# ezo_single.net
KiCad netlist of a schematic drawn in EAGLE
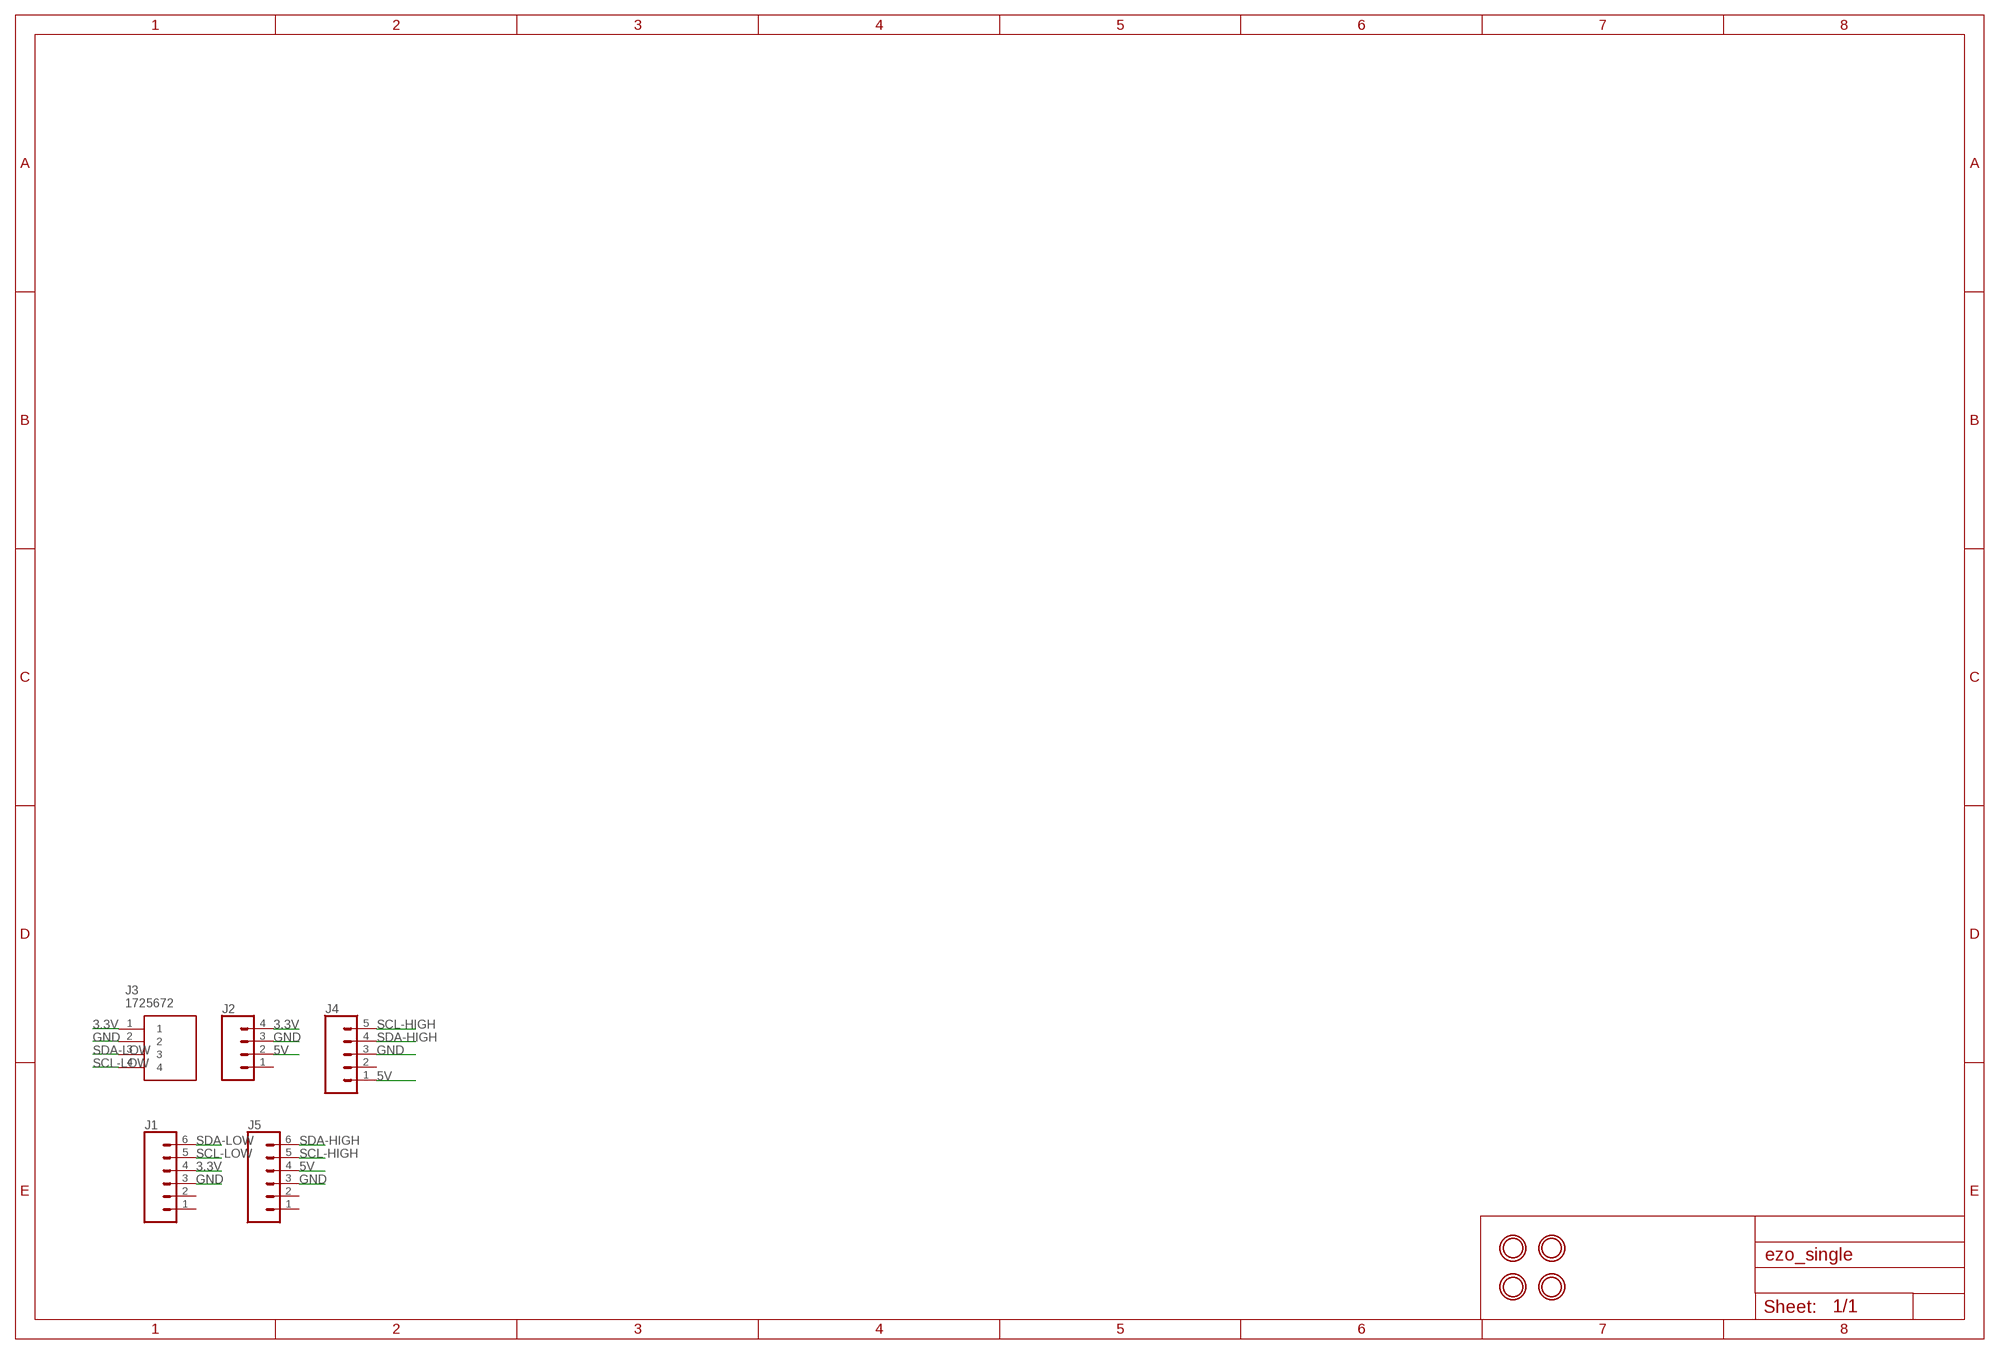
[diagram p0: schematic, sheet 1]

(export (version "E")
  (design (tool "Eeschema 10.0.6"))
  (components
    (comp (ref "J1")
      (value "CONN_06SILK_FEMALE_PTH")
      (footprint "eagle-import:1X06")
      (libsource (lib "eagle-import") (part "CONN_06SILK_FEMALE_PTH"))
    )
    (comp (ref "J2")
      (value "CONN_04PTH")
      (footprint "eagle-import:1X04")
      (libsource (lib "eagle-import") (part "CONN_04PTH"))
    )
    (comp (ref "J3")
      (value "1725672")
      (footprint "eagle-import:1725672")
      (fields (field (name "MOUSER_PART_NUMBER") "651-1725672"))
      (libsource (lib "eagle-import") (part "1725672"))
    )
    (comp (ref "J4")
      (value "CONN_05PTH")
      (footprint "eagle-import:1X05")
      (libsource (lib "eagle-import") (part "CONN_05PTH"))
    )
    (comp (ref "J5")
      (value "CONN_06SILK_FEMALE_PTH")
      (footprint "eagle-import:1X06")
      (libsource (lib "eagle-import") (part "CONN_06SILK_FEMALE_PTH"))
    )
    (comp (ref "U$1")
      (value "MOUNTINGHOLE2.5")
      (footprint "eagle-import:MOUNTINGHOLE_2.5_PLATED")
      (libsource (lib "eagle-import") (part "MOUNTINGHOLE2.5"))
    )
    (comp (ref "U$2")
      (value "MOUNTINGHOLE2.5")
      (footprint "eagle-import:MOUNTINGHOLE_2.5_PLATED")
      (libsource (lib "eagle-import") (part "MOUNTINGHOLE2.5"))
    )
    (comp (ref "U$3")
      (value "MOUNTINGHOLE2.5")
      (footprint "eagle-import:MOUNTINGHOLE_2.5_PLATED")
      (libsource (lib "eagle-import") (part "MOUNTINGHOLE2.5"))
    )
    (comp (ref "U$4")
      (value "MOUNTINGHOLE2.5")
      (footprint "eagle-import:MOUNTINGHOLE_2.5_PLATED")
      (libsource (lib "eagle-import") (part "MOUNTINGHOLE2.5"))
    )
  )
  (nets
    (net (code "1") (name "/3.3V") (class "Default")
      (node (ref "J1") (pin "4") (pinfunction "4_4") (pintype "passive"))
      (node (ref "J2") (pin "4") (pinfunction "4_4") (pintype "passive"))
      (node (ref "J3") (pin "1") (pinfunction "1_1") (pintype "bidirectional"))
    )
    (net (code "2") (name "/5V") (class "Default")
      (node (ref "J2") (pin "2") (pinfunction "2_2") (pintype "passive"))
      (node (ref "J4") (pin "1") (pinfunction "1_1") (pintype "passive"))
      (node (ref "J5") (pin "4") (pinfunction "4_4") (pintype "passive"))
    )
    (net (code "3") (name "/GND") (class "Default")
      (node (ref "J1") (pin "3") (pinfunction "3_3") (pintype "passive"))
      (node (ref "J2") (pin "3") (pinfunction "3_3") (pintype "passive"))
      (node (ref "J3") (pin "2") (pinfunction "2_2") (pintype "bidirectional"))
      (node (ref "J4") (pin "3") (pinfunction "3_3") (pintype "passive"))
      (node (ref "J5") (pin "3") (pinfunction "3_3") (pintype "passive"))
    )
    (net (code "4") (name "/SCL-HIGH") (class "Default")
      (node (ref "J4") (pin "5") (pinfunction "5_5") (pintype "passive"))
      (node (ref "J5") (pin "5") (pinfunction "5_5") (pintype "passive"))
    )
    (net (code "5") (name "/SCL-LOW") (class "Default")
      (node (ref "J1") (pin "5") (pinfunction "5_5") (pintype "passive"))
      (node (ref "J3") (pin "4") (pinfunction "4_4") (pintype "bidirectional"))
    )
    (net (code "6") (name "/SDA-HIGH") (class "Default")
      (node (ref "J4") (pin "4") (pinfunction "4_4") (pintype "passive"))
      (node (ref "J5") (pin "6") (pinfunction "6_6") (pintype "passive"))
    )
    (net (code "7") (name "/SDA-LOW") (class "Default")
      (node (ref "J1") (pin "6") (pinfunction "6_6") (pintype "passive"))
      (node (ref "J3") (pin "3") (pinfunction "3_3") (pintype "bidirectional"))
    )
    (net (code "8") (name "unconnected-(J1-Pad1)") (class "Default")
      (node (ref "J1") (pin "1") (pinfunction "1_1") (pintype "passive"))
    )
    (net (code "9") (name "unconnected-(J1-Pad2)") (class "Default")
      (node (ref "J1") (pin "2") (pinfunction "2_2") (pintype "passive"))
    )
    (net (code "10") (name "unconnected-(J2-Pad1)") (class "Default")
      (node (ref "J2") (pin "1") (pinfunction "1_1") (pintype "passive"))
    )
    (net (code "11") (name "unconnected-(J4-Pad2)") (class "Default")
      (node (ref "J4") (pin "2") (pinfunction "2_2") (pintype "passive"))
    )
    (net (code "12") (name "unconnected-(J5-Pad1)") (class "Default")
      (node (ref "J5") (pin "1") (pinfunction "1_1") (pintype "passive"))
    )
    (net (code "13") (name "unconnected-(J5-Pad2)") (class "Default")
      (node (ref "J5") (pin "2") (pinfunction "2_2") (pintype "passive"))
    )
  )
)
